# Equilizer_Protoboard.net
KiCad netlist of a schematic drawn in EAGLE
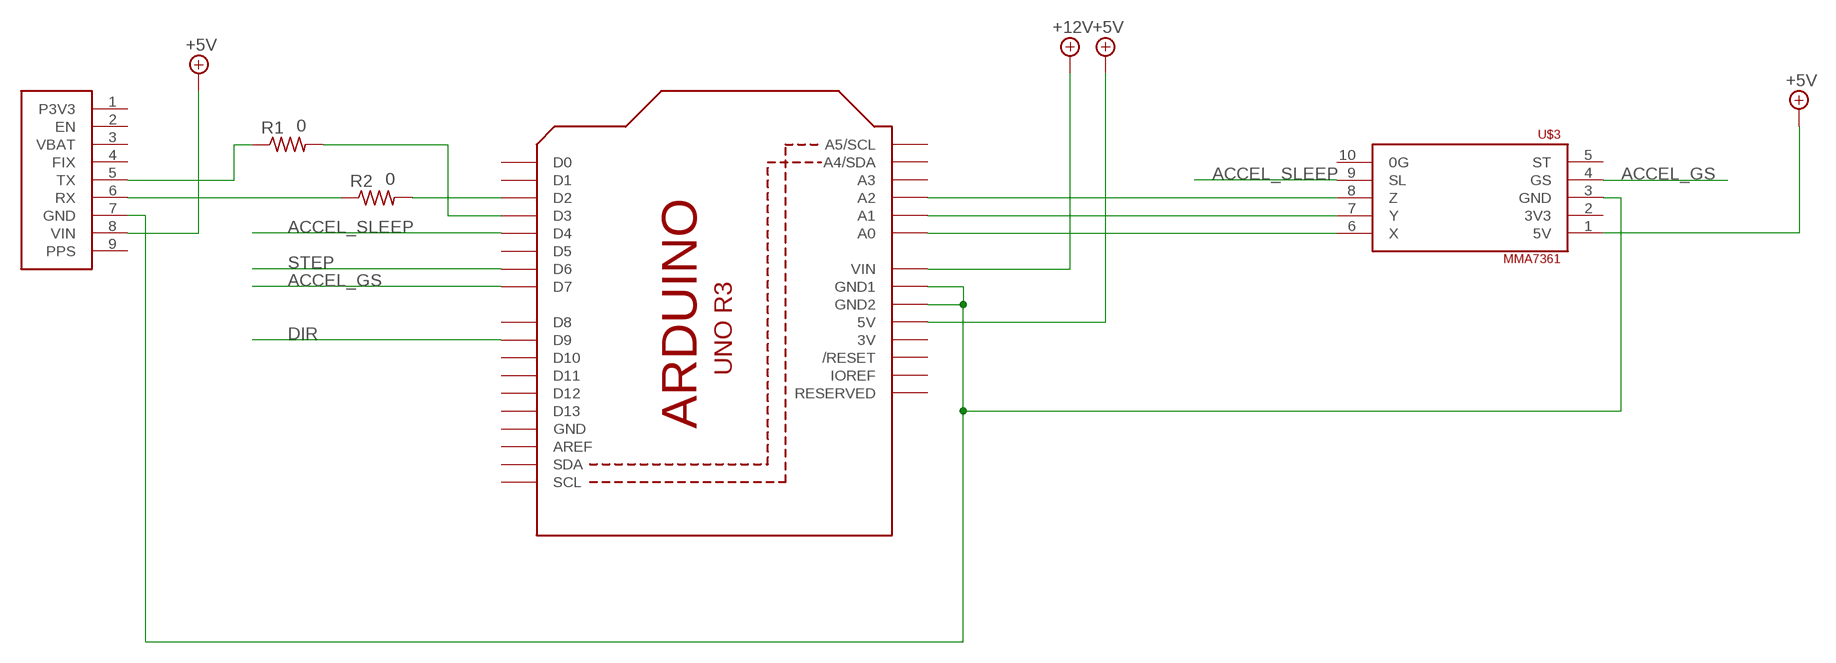
[diagram p0: schematic, sheet 1]

(export (version "E")
  (design (tool "Eeschema 10.0.6"))
  (components
    (comp (ref "R1")
      (value "0")
      (footprint "eagle-import:0204_7")
      (libsource (lib "eagle-import") (part "R-US_0204/7"))
    )
    (comp (ref "R2")
      (value "0")
      (footprint "eagle-import:0204_7")
      (libsource (lib "eagle-import") (part "R-US_0204/7"))
    )
    (comp (ref "U$3")
      (value "MMA7361")
      (footprint "eagle-import:MMA7361")
      (libsource (lib "eagle-import") (part "MMA7361"))
    )
    (comp (ref "U$4")
      (value "ADAFRUIT_GPS_MODULE")
      (footprint "eagle-import:ADAFRUIT_GPS_BREAKOUT")
      (libsource (lib "eagle-import") (part "ADAFRUIT_GPS_MODULE"))
    )
    (comp (ref "U1")
      (value "ARDUINOR3-BPLACE")
      (footprint "eagle-import:ARDUINOR3-BPLACE")
      (libsource (lib "eagle-import") (part "ARDUINOR3-BPLACE"))
    )
  )
  (nets
    (net (code "1") (name "+5V") (class "Default")
      (node (ref "U$3") (pin "1") (pinfunction "5V_1") (pintype "bidirectional"))
      (node (ref "U$4") (pin "8") (pinfunction "VIN_8") (pintype "bidirectional"))
      (node (ref "U1") (pin "5V") (pinfunction "5V_5V") (pintype "power_in"))
    )
    (net (code "2") (name "+12V") (class "Default")
      (node (ref "U1") (pin "VIN") (pinfunction "VIN_VIN") (pintype "power_in"))
    )
    (net (code "3") (name "/3V") (class "Default")
      (node (ref "U1") (pin "3V") (pinfunction "3V_3V") (pintype "power_in"))
    )
    (net (code "4") (name "/ACCEL_GS") (class "Default")
      (node (ref "U$3") (pin "4") (pinfunction "GS_4") (pintype "bidirectional"))
      (node (ref "U1") (pin "D7") (pinfunction "D7_D7") (pintype "bidirectional"))
    )
    (net (code "5") (name "/ACCEL_SLEEP") (class "Default")
      (node (ref "U$3") (pin "9") (pinfunction "SL_9") (pintype "bidirectional"))
      (node (ref "U1") (pin "D4") (pinfunction "D4_D4") (pintype "bidirectional"))
    )
    (net (code "6") (name "/DIR") (class "Default")
      (node (ref "U1") (pin "D9") (pinfunction "D9_D9") (pintype "bidirectional"))
    )
    (net (code "7") (name "/GND") (class "Default")
      (node (ref "U1") (pin "GND") (pinfunction "GND_GND") (pintype "power_in"))
    )
    (net (code "8") (name "/STEP") (class "Default")
      (node (ref "U1") (pin "D6") (pinfunction "D6_D6") (pintype "bidirectional"))
    )
    (net (code "9") (name "Net-(R1-Pad2)") (class "Default")
      (node (ref "R1") (pin "2") (pinfunction "2_2") (pintype "passive"))
      (node (ref "U1") (pin "D3") (pinfunction "D3_D3") (pintype "bidirectional"))
    )
    (net (code "10") (name "Net-(R2-Pad2)") (class "Default")
      (node (ref "R2") (pin "2") (pinfunction "2_2") (pintype "passive"))
      (node (ref "U1") (pin "D2") (pinfunction "D2_D2") (pintype "bidirectional"))
    )
    (net (code "11") (name "Net-(U$3-GND)") (class "Default")
      (node (ref "U$3") (pin "3") (pinfunction "GND_3") (pintype "bidirectional"))
      (node (ref "U$4") (pin "7") (pinfunction "GND_7") (pintype "bidirectional"))
      (node (ref "U1") (pin "GND1") (pinfunction "GND1_GND1") (pintype "power_in"))
      (node (ref "U1") (pin "GND2") (pinfunction "GND2_GND2") (pintype "power_in"))
    )
    (net (code "12") (name "Net-(U$3-X)") (class "Default")
      (node (ref "U$3") (pin "6") (pinfunction "X_6") (pintype "bidirectional"))
      (node (ref "U1") (pin "A0") (pinfunction "A0_A0") (pintype "bidirectional"))
    )
    (net (code "13") (name "Net-(U$3-Y)") (class "Default")
      (node (ref "U$3") (pin "7") (pinfunction "Y_7") (pintype "bidirectional"))
      (node (ref "U1") (pin "A1") (pinfunction "A1_A1") (pintype "bidirectional"))
    )
    (net (code "14") (name "Net-(U$3-Z)") (class "Default")
      (node (ref "U$3") (pin "8") (pinfunction "Z_8") (pintype "bidirectional"))
      (node (ref "U1") (pin "A2") (pinfunction "A2_A2") (pintype "bidirectional"))
    )
    (net (code "15") (name "Net-(U$4-RX)") (class "Default")
      (node (ref "R2") (pin "1") (pinfunction "1_1") (pintype "passive"))
      (node (ref "U$4") (pin "6") (pinfunction "RX_6") (pintype "bidirectional"))
    )
    (net (code "16") (name "Net-(U$4-TX)") (class "Default")
      (node (ref "R1") (pin "1") (pinfunction "1_1") (pintype "passive"))
      (node (ref "U$4") (pin "5") (pinfunction "TX_5") (pintype "bidirectional"))
    )
    (net (code "17") (name "unconnected-(U$3-0G-Pad10)") (class "Default")
      (node (ref "U$3") (pin "10") (pinfunction "0G_10") (pintype "bidirectional"))
    )
    (net (code "18") (name "unconnected-(U$3-3V3-Pad2)") (class "Default")
      (node (ref "U$3") (pin "2") (pinfunction "3V3_2") (pintype "bidirectional"))
    )
    (net (code "19") (name "unconnected-(U$3-ST-Pad5)") (class "Default")
      (node (ref "U$3") (pin "5") (pinfunction "ST_5") (pintype "bidirectional"))
    )
    (net (code "20") (name "unconnected-(U$4-EN-Pad2)") (class "Default")
      (node (ref "U$4") (pin "2") (pinfunction "EN_2") (pintype "bidirectional"))
    )
    (net (code "21") (name "unconnected-(U$4-FIX-Pad4)") (class "Default")
      (node (ref "U$4") (pin "4") (pinfunction "FIX_4") (pintype "bidirectional"))
    )
    (net (code "22") (name "unconnected-(U$4-P3V3-Pad1)") (class "Default")
      (node (ref "U$4") (pin "1") (pinfunction "P3V3_1") (pintype "bidirectional"))
    )
    (net (code "23") (name "unconnected-(U$4-PPS-Pad9)") (class "Default")
      (node (ref "U$4") (pin "9") (pinfunction "PPS_9") (pintype "bidirectional"))
    )
    (net (code "24") (name "unconnected-(U$4-VBAT-Pad3)") (class "Default")
      (node (ref "U$4") (pin "3") (pinfunction "VBAT_3") (pintype "bidirectional"))
    )
    (net (code "25") (name "unconnected-(U1-A4{slash}SDA-PadA4)") (class "Default")
      (node (ref "U1") (pin "A4") (pinfunction "A4/SDA_A4") (pintype "bidirectional"))
    )
    (net (code "26") (name "unconnected-(U1-A5{slash}SCL-PadA5)") (class "Default")
      (node (ref "U1") (pin "A5") (pinfunction "A5/SCL_A5") (pintype "bidirectional"))
    )
    (net (code "27") (name "unconnected-(U1-PadA3)") (class "Default")
      (node (ref "U1") (pin "A3") (pinfunction "A3_A3") (pintype "bidirectional"))
    )
    (net (code "28") (name "unconnected-(U1-PadAREF)") (class "Default")
      (node (ref "U1") (pin "AREF") (pinfunction "AREF_AREF") (pintype "bidirectional"))
    )
    (net (code "29") (name "unconnected-(U1-PadD0)") (class "Default")
      (node (ref "U1") (pin "D0") (pinfunction "D0_D0") (pintype "bidirectional"))
    )
    (net (code "30") (name "unconnected-(U1-PadD1)") (class "Default")
      (node (ref "U1") (pin "D1") (pinfunction "D1_D1") (pintype "bidirectional"))
    )
    (net (code "31") (name "unconnected-(U1-PadD5)") (class "Default")
      (node (ref "U1") (pin "D5") (pinfunction "D5_D5") (pintype "bidirectional"))
    )
    (net (code "32") (name "unconnected-(U1-PadD8)") (class "Default")
      (node (ref "U1") (pin "D8") (pinfunction "D8_D8") (pintype "bidirectional"))
    )
    (net (code "33") (name "unconnected-(U1-PadD10)") (class "Default")
      (node (ref "U1") (pin "D10") (pinfunction "D10_D10") (pintype "bidirectional"))
    )
    (net (code "34") (name "unconnected-(U1-PadD11)") (class "Default")
      (node (ref "U1") (pin "D11") (pinfunction "D11_D11") (pintype "bidirectional"))
    )
    (net (code "35") (name "unconnected-(U1-PadD12)") (class "Default")
      (node (ref "U1") (pin "D12") (pinfunction "D12_D12") (pintype "bidirectional"))
    )
    (net (code "36") (name "unconnected-(U1-PadD13)") (class "Default")
      (node (ref "U1") (pin "D13") (pinfunction "D13_D13") (pintype "bidirectional"))
    )
    (net (code "37") (name "unconnected-(U1-PadIOREF)") (class "Default")
      (node (ref "U1") (pin "IOREF") (pinfunction "IOREF_IOREF") (pintype "output"))
    )
    (net (code "38") (name "unconnected-(U1-PadRESERVED)") (class "Default")
      (node (ref "U1") (pin "RESERVED") (pinfunction "RESERVED_RESERVED") (pintype "no_connect"))
    )
    (net (code "39") (name "unconnected-(U1-PadSCL)") (class "Default")
      (node (ref "U1") (pin "SCL") (pinfunction "SCL_SCL") (pintype "bidirectional"))
    )
    (net (code "40") (name "unconnected-(U1-PadSDA)") (class "Default")
      (node (ref "U1") (pin "SDA") (pinfunction "SDA_SDA") (pintype "bidirectional"))
    )
    (net (code "41") (name "unconnected-(U1-{slash}RESET-PadRESET)") (class "Default")
      (node (ref "U1") (pin "RESET") (pinfunction "/RESET_RESET") (pintype "bidirectional"))
    )
  )
)
